# PanelPCB.net
KiCad netlist of a schematic drawn in EAGLE
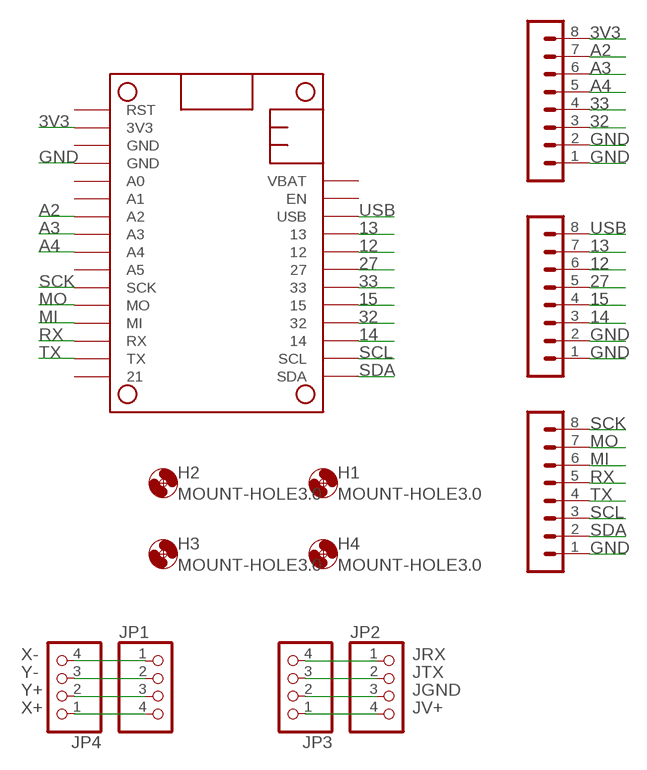
[diagram p0: schematic, sheet 1]

(export (version "E")
  (design (tool "Eeschema 10.0.6"))
  (components
    (comp (ref "H1")
      (value "MOUNT-HOLE3.0")
      (footprint "eagle-import:3,0")
      (libsource (lib "eagle-import") (part "MOUNT-HOLE3.0"))
    )
    (comp (ref "H2")
      (value "MOUNT-HOLE3.0")
      (footprint "eagle-import:3,0")
      (libsource (lib "eagle-import") (part "MOUNT-HOLE3.0"))
    )
    (comp (ref "H3")
      (value "MOUNT-HOLE3.0")
      (footprint "eagle-import:3,0")
      (libsource (lib "eagle-import") (part "MOUNT-HOLE3.0"))
    )
    (comp (ref "H4")
      (value "MOUNT-HOLE3.0")
      (footprint "eagle-import:3,0")
      (libsource (lib "eagle-import") (part "MOUNT-HOLE3.0"))
    )
    (comp (ref "JP1")
      (value "PINHD-1X4")
      (footprint "eagle-import:1X04")
      (libsource (lib "eagle-import") (part "PINHD-1X4"))
    )
    (comp (ref "JP2")
      (value "PINHD-1X4")
      (footprint "eagle-import:1X04")
      (libsource (lib "eagle-import") (part "PINHD-1X4"))
    )
    (comp (ref "JP3")
      (value "PINHD-1X4")
      (footprint "eagle-import:1X04")
      (libsource (lib "eagle-import") (part "PINHD-1X4"))
    )
    (comp (ref "JP4")
      (value "PINHD-1X4")
      (footprint "eagle-import:1X04")
      (libsource (lib "eagle-import") (part "PINHD-1X4"))
    )
    (comp (ref "M1")
      (value "RARNDT-MISCELANEOUS_FEATHERBOARD_ESP32FETHERWING_DIM_ESP32")
      (footprint "eagle-import:RARNDT-MISCELANEOUS_FEATHERBOARD_ESP32")
      (libsource (lib "eagle-import") (part "RARNDT-MISCELANEOUS_FEATHERBOARD_ESP32FETHERWING_DIM_ESP32"))
    )
    (comp (ref "SV1")
      (value "MA08-1")
      (footprint "eagle-import:MA08-1")
      (libsource (lib "eagle-import") (part "MA08-1"))
    )
    (comp (ref "SV2")
      (value "MA08-1")
      (footprint "eagle-import:MA08-1")
      (libsource (lib "eagle-import") (part "MA08-1"))
    )
    (comp (ref "SV3")
      (value "MA08-1")
      (footprint "eagle-import:MA08-1")
      (libsource (lib "eagle-import") (part "MA08-1"))
    )
  )
  (nets
    (net (code "1") (name "/3V3") (class "Default")
      (node (ref "M1") (pin "2") (pinfunction "3V3_2") (pintype "power_in"))
      (node (ref "SV1") (pin "8") (pinfunction "8_8") (pintype "passive"))
    )
    (net (code "2") (name "/12") (class "Default")
      (node (ref "M1") (pin "24") (pinfunction "12_24") (pintype "bidirectional"))
      (node (ref "SV2") (pin "6") (pinfunction "6_6") (pintype "passive"))
    )
    (net (code "3") (name "/13") (class "Default")
      (node (ref "M1") (pin "25") (pinfunction "13_25") (pintype "bidirectional"))
      (node (ref "SV2") (pin "7") (pinfunction "7_7") (pintype "passive"))
    )
    (net (code "4") (name "/14") (class "Default")
      (node (ref "M1") (pin "19") (pinfunction "14_19") (pintype "bidirectional"))
      (node (ref "SV2") (pin "3") (pinfunction "3_3") (pintype "passive"))
    )
    (net (code "5") (name "/15") (class "Default")
      (node (ref "M1") (pin "21") (pinfunction "15_21") (pintype "bidirectional"))
      (node (ref "SV2") (pin "4") (pinfunction "4_4") (pintype "passive"))
    )
    (net (code "6") (name "/27") (class "Default")
      (node (ref "M1") (pin "23") (pinfunction "27_23") (pintype "bidirectional"))
      (node (ref "SV2") (pin "5") (pinfunction "5_5") (pintype "passive"))
    )
    (net (code "7") (name "/32") (class "Default")
      (node (ref "M1") (pin "20") (pinfunction "32_20") (pintype "bidirectional"))
      (node (ref "SV1") (pin "3") (pinfunction "3_3") (pintype "passive"))
    )
    (net (code "8") (name "/33") (class "Default")
      (node (ref "M1") (pin "22") (pinfunction "33_22") (pintype "bidirectional"))
      (node (ref "SV1") (pin "4") (pinfunction "4_4") (pintype "passive"))
    )
    (net (code "9") (name "/A2") (class "Default")
      (node (ref "M1") (pin "7") (pinfunction "A2_7") (pintype "bidirectional"))
      (node (ref "SV1") (pin "7") (pinfunction "7_7") (pintype "passive"))
    )
    (net (code "10") (name "/A3") (class "Default")
      (node (ref "M1") (pin "8") (pinfunction "A3_8") (pintype "bidirectional"))
      (node (ref "SV1") (pin "6") (pinfunction "6_6") (pintype "passive"))
    )
    (net (code "11") (name "/A4") (class "Default")
      (node (ref "M1") (pin "9") (pinfunction "A4_9") (pintype "bidirectional"))
      (node (ref "SV1") (pin "5") (pinfunction "5_5") (pintype "passive"))
    )
    (net (code "12") (name "/GND") (class "Default")
      (node (ref "M1") (pin "4") (pinfunction "GND_4") (pintype "power_in"))
      (node (ref "SV1") (pin "1") (pinfunction "1_1") (pintype "passive"))
      (node (ref "SV1") (pin "2") (pinfunction "2_2") (pintype "passive"))
      (node (ref "SV2") (pin "1") (pinfunction "1_1") (pintype "passive"))
      (node (ref "SV2") (pin "2") (pinfunction "2_2") (pintype "passive"))
      (node (ref "SV3") (pin "1") (pinfunction "1_1") (pintype "passive"))
    )
    (net (code "13") (name "/JGND") (class "Default")
      (node (ref "JP2") (pin "3") (pinfunction "3_3") (pintype "passive"))
      (node (ref "JP3") (pin "2") (pinfunction "2_2") (pintype "passive"))
    )
    (net (code "14") (name "/JRX") (class "Default")
      (node (ref "JP2") (pin "1") (pinfunction "1_1") (pintype "passive"))
      (node (ref "JP3") (pin "4") (pinfunction "4_4") (pintype "passive"))
    )
    (net (code "15") (name "/JTX") (class "Default")
      (node (ref "JP2") (pin "2") (pinfunction "2_2") (pintype "passive"))
      (node (ref "JP3") (pin "3") (pinfunction "3_3") (pintype "passive"))
    )
    (net (code "16") (name "/JV+") (class "Default")
      (node (ref "JP2") (pin "4") (pinfunction "4_4") (pintype "passive"))
      (node (ref "JP3") (pin "1") (pinfunction "1_1") (pintype "passive"))
    )
    (net (code "17") (name "/MI") (class "Default")
      (node (ref "M1") (pin "13") (pinfunction "MI_13") (pintype "bidirectional"))
      (node (ref "SV3") (pin "6") (pinfunction "6_6") (pintype "passive"))
    )
    (net (code "18") (name "/MO") (class "Default")
      (node (ref "M1") (pin "12") (pinfunction "MO_12") (pintype "bidirectional"))
      (node (ref "SV3") (pin "7") (pinfunction "7_7") (pintype "passive"))
    )
    (net (code "19") (name "/RX") (class "Default")
      (node (ref "M1") (pin "14") (pinfunction "RX_14") (pintype "bidirectional"))
      (node (ref "SV3") (pin "5") (pinfunction "5_5") (pintype "passive"))
    )
    (net (code "20") (name "/SCK") (class "Default")
      (node (ref "M1") (pin "11") (pinfunction "SCK_11") (pintype "bidirectional"))
      (node (ref "SV3") (pin "8") (pinfunction "8_8") (pintype "passive"))
    )
    (net (code "21") (name "/SCL") (class "Default")
      (node (ref "M1") (pin "18") (pinfunction "SCL_18") (pintype "bidirectional"))
      (node (ref "SV3") (pin "3") (pinfunction "3_3") (pintype "passive"))
    )
    (net (code "22") (name "/SDA") (class "Default")
      (node (ref "M1") (pin "17") (pinfunction "SDA_17") (pintype "bidirectional"))
      (node (ref "SV3") (pin "2") (pinfunction "2_2") (pintype "passive"))
    )
    (net (code "23") (name "/TX") (class "Default")
      (node (ref "M1") (pin "15") (pinfunction "TX_15") (pintype "bidirectional"))
      (node (ref "SV3") (pin "4") (pinfunction "4_4") (pintype "passive"))
    )
    (net (code "24") (name "/USB") (class "Default")
      (node (ref "M1") (pin "26") (pinfunction "USB_26") (pintype "power_in"))
      (node (ref "SV2") (pin "8") (pinfunction "8_8") (pintype "passive"))
    )
    (net (code "25") (name "/VBAT") (class "Default")
      (node (ref "M1") (pin "28") (pinfunction "VBAT_28") (pintype "power_in"))
    )
    (net (code "26") (name "/X+") (class "Default")
      (node (ref "JP1") (pin "4") (pinfunction "4_4") (pintype "passive"))
      (node (ref "JP4") (pin "1") (pinfunction "1_1") (pintype "passive"))
    )
    (net (code "27") (name "/X-") (class "Default")
      (node (ref "JP1") (pin "1") (pinfunction "1_1") (pintype "passive"))
      (node (ref "JP4") (pin "4") (pinfunction "4_4") (pintype "passive"))
    )
    (net (code "28") (name "/Y+") (class "Default")
      (node (ref "JP1") (pin "3") (pinfunction "3_3") (pintype "passive"))
      (node (ref "JP4") (pin "2") (pinfunction "2_2") (pintype "passive"))
    )
    (net (code "29") (name "/Y-") (class "Default")
      (node (ref "JP1") (pin "2") (pinfunction "2_2") (pintype "passive"))
      (node (ref "JP4") (pin "3") (pinfunction "3_3") (pintype "passive"))
    )
    (net (code "30") (name "unconnected-(M1-21-Pad16)") (class "Default")
      (node (ref "M1") (pin "16") (pinfunction "21_16") (pintype "passive"))
    )
    (net (code "31") (name "unconnected-(M1-A0-Pad5)") (class "Default")
      (node (ref "M1") (pin "5") (pinfunction "A0_5") (pintype "bidirectional"))
    )
    (net (code "32") (name "unconnected-(M1-A1-Pad6)") (class "Default")
      (node (ref "M1") (pin "6") (pinfunction "A1_6") (pintype "bidirectional"))
    )
    (net (code "33") (name "unconnected-(M1-A5-Pad10)") (class "Default")
      (node (ref "M1") (pin "10") (pinfunction "A5_10") (pintype "bidirectional"))
    )
    (net (code "34") (name "unconnected-(M1-EN-Pad27)") (class "Default")
      (node (ref "M1") (pin "27") (pinfunction "EN_27") (pintype "passive"))
    )
    (net (code "35") (name "unconnected-(M1-GND-Pad3)") (class "Default")
      (node (ref "M1") (pin "3") (pinfunction "GND_3") (pintype "passive"))
    )
    (net (code "36") (name "unconnected-(M1-RST-Pad1)") (class "Default")
      (node (ref "M1") (pin "1") (pinfunction "RST_1") (pintype "input"))
    )
  )
)
